# Channel_Display_v1.net
KiCad netlist of a schematic drawn in EAGLE
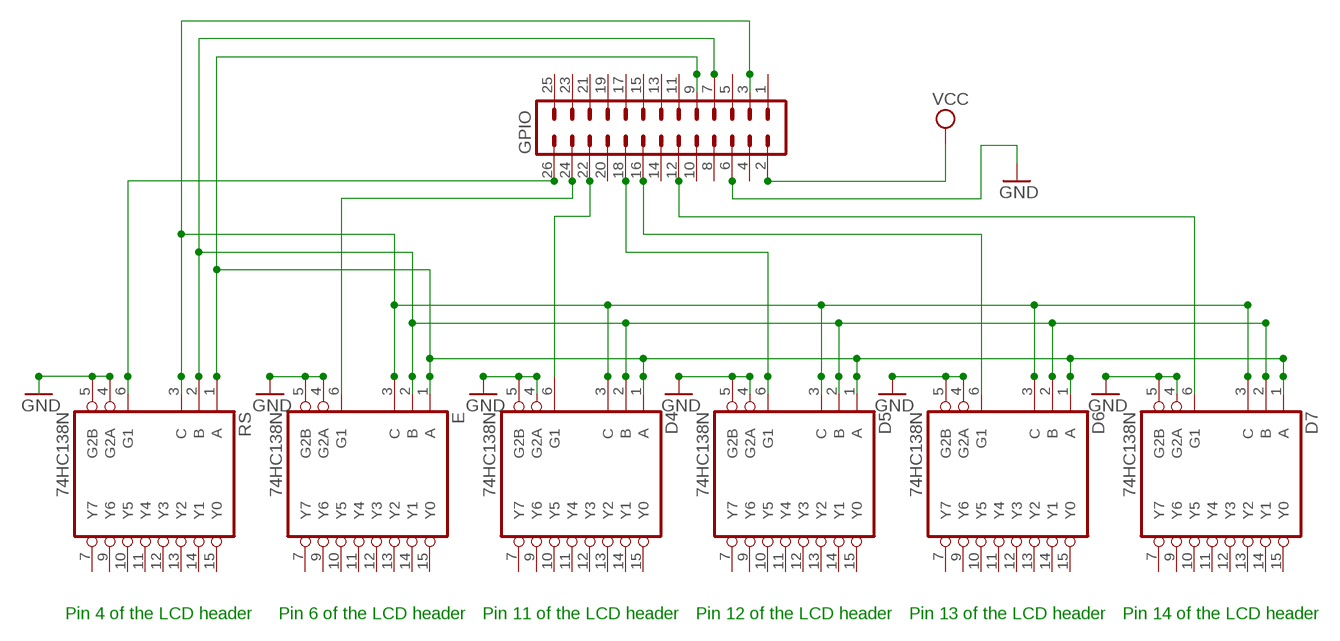
[diagram p0: schematic, sheet 1]

(export (version "E")
  (design (tool "Eeschema 10.0.6"))
  (components
    (comp (ref "D4")
      (value "74HC138N")
      (footprint "eagle-import:DIL16")
      (libsource (lib "eagle-import") (part "74138NHC"))
    )
    (comp (ref "D5")
      (value "74HC138N")
      (footprint "eagle-import:DIL16")
      (libsource (lib "eagle-import") (part "74138NHC"))
    )
    (comp (ref "D6")
      (value "74HC138N")
      (footprint "eagle-import:DIL16")
      (libsource (lib "eagle-import") (part "74138NHC"))
    )
    (comp (ref "D7")
      (value "74HC138N")
      (footprint "eagle-import:DIL16")
      (libsource (lib "eagle-import") (part "74138NHC"))
    )
    (comp (ref "E")
      (value "74HC138N")
      (footprint "eagle-import:DIL16")
      (libsource (lib "eagle-import") (part "74138NHC"))
    )
    (comp (ref "GPIO")
      (value "MA13-2")
      (footprint "eagle-import:MA13-2")
      (libsource (lib "eagle-import") (part "MA13-2"))
    )
    (comp (ref "RS")
      (value "74HC138N")
      (footprint "eagle-import:DIL16")
      (libsource (lib "eagle-import") (part "74138NHC"))
    )
  )
  (nets
    (net (code "1") (name "GND") (class "Default")
      (node (ref "D4") (pin "4") (pinfunction "G2A_4") (pintype "input"))
      (node (ref "D4") (pin "5") (pinfunction "G2B_5") (pintype "input"))
      (node (ref "D5") (pin "4") (pinfunction "G2A_4") (pintype "input"))
      (node (ref "D5") (pin "5") (pinfunction "G2B_5") (pintype "input"))
      (node (ref "D6") (pin "4") (pinfunction "G2A_4") (pintype "input"))
      (node (ref "D6") (pin "5") (pinfunction "G2B_5") (pintype "input"))
      (node (ref "D7") (pin "4") (pinfunction "G2A_4") (pintype "input"))
      (node (ref "D7") (pin "5") (pinfunction "G2B_5") (pintype "input"))
      (node (ref "E") (pin "4") (pinfunction "G2A_4") (pintype "input"))
      (node (ref "E") (pin "5") (pinfunction "G2B_5") (pintype "input"))
      (node (ref "GPIO") (pin "6") (pinfunction "6_6") (pintype "passive"))
      (node (ref "RS") (pin "4") (pinfunction "G2A_4") (pintype "input"))
      (node (ref "RS") (pin "5") (pinfunction "G2B_5") (pintype "input"))
    )
    (net (code "2") (name "Net-(D4A-A)") (class "Default")
      (node (ref "D4") (pin "1") (pinfunction "A_1") (pintype "input"))
      (node (ref "D5") (pin "1") (pinfunction "A_1") (pintype "input"))
      (node (ref "D6") (pin "1") (pinfunction "A_1") (pintype "input"))
      (node (ref "D7") (pin "1") (pinfunction "A_1") (pintype "input"))
      (node (ref "E") (pin "1") (pinfunction "A_1") (pintype "input"))
      (node (ref "GPIO") (pin "9") (pinfunction "9_9") (pintype "passive"))
      (node (ref "RS") (pin "1") (pinfunction "A_1") (pintype "input"))
    )
    (net (code "3") (name "Net-(D4A-B)") (class "Default")
      (node (ref "D4") (pin "2") (pinfunction "B_2") (pintype "input"))
      (node (ref "D5") (pin "2") (pinfunction "B_2") (pintype "input"))
      (node (ref "D6") (pin "2") (pinfunction "B_2") (pintype "input"))
      (node (ref "D7") (pin "2") (pinfunction "B_2") (pintype "input"))
      (node (ref "E") (pin "2") (pinfunction "B_2") (pintype "input"))
      (node (ref "GPIO") (pin "7") (pinfunction "7_7") (pintype "passive"))
      (node (ref "RS") (pin "2") (pinfunction "B_2") (pintype "input"))
    )
    (net (code "4") (name "Net-(D4A-C)") (class "Default")
      (node (ref "D4") (pin "3") (pinfunction "C_3") (pintype "input"))
      (node (ref "D5") (pin "3") (pinfunction "C_3") (pintype "input"))
      (node (ref "D6") (pin "3") (pinfunction "C_3") (pintype "input"))
      (node (ref "D7") (pin "3") (pinfunction "C_3") (pintype "input"))
      (node (ref "E") (pin "3") (pinfunction "C_3") (pintype "input"))
      (node (ref "GPIO") (pin "3") (pinfunction "3_3") (pintype "passive"))
      (node (ref "RS") (pin "3") (pinfunction "C_3") (pintype "input"))
    )
    (net (code "5") (name "Net-(D4A-G1)") (class "Default")
      (node (ref "D4") (pin "6") (pinfunction "G1_6") (pintype "input"))
      (node (ref "GPIO") (pin "22") (pinfunction "22_22") (pintype "passive"))
    )
    (net (code "6") (name "Net-(D5A-G1)") (class "Default")
      (node (ref "D5") (pin "6") (pinfunction "G1_6") (pintype "input"))
      (node (ref "GPIO") (pin "18") (pinfunction "18_18") (pintype "passive"))
    )
    (net (code "7") (name "Net-(RSA-G1)") (class "Default")
      (node (ref "GPIO") (pin "26") (pinfunction "26_26") (pintype "passive"))
      (node (ref "RS") (pin "6") (pinfunction "G1_6") (pintype "input"))
    )
    (net (code "8") (name "VCC") (class "Default")
      (node (ref "GPIO") (pin "2") (pinfunction "2_2") (pintype "passive"))
    )
    (net (code "9") (name "unconnected-(D4A-Y0-Pad15)") (class "Default")
      (node (ref "D4") (pin "15") (pinfunction "Y0_15") (pintype "output"))
    )
    (net (code "10") (name "unconnected-(D4A-Y1-Pad14)") (class "Default")
      (node (ref "D4") (pin "14") (pinfunction "Y1_14") (pintype "output"))
    )
    (net (code "11") (name "unconnected-(D4A-Y2-Pad13)") (class "Default")
      (node (ref "D4") (pin "13") (pinfunction "Y2_13") (pintype "output"))
    )
    (net (code "12") (name "unconnected-(D4A-Y3-Pad12)") (class "Default")
      (node (ref "D4") (pin "12") (pinfunction "Y3_12") (pintype "output"))
    )
    (net (code "13") (name "unconnected-(D4A-Y4-Pad11)") (class "Default")
      (node (ref "D4") (pin "11") (pinfunction "Y4_11") (pintype "output"))
    )
    (net (code "14") (name "unconnected-(D4A-Y5-Pad10)") (class "Default")
      (node (ref "D4") (pin "10") (pinfunction "Y5_10") (pintype "output"))
    )
    (net (code "15") (name "unconnected-(D4A-Y6-Pad9)") (class "Default")
      (node (ref "D4") (pin "9") (pinfunction "Y6_9") (pintype "output"))
    )
    (net (code "16") (name "unconnected-(D4A-Y7-Pad7)") (class "Default")
      (node (ref "D4") (pin "7") (pinfunction "Y7_7") (pintype "output"))
    )
    (net (code "17") (name "unconnected-(D5A-Y0-Pad15)") (class "Default")
      (node (ref "D5") (pin "15") (pinfunction "Y0_15") (pintype "output"))
    )
    (net (code "18") (name "unconnected-(D5A-Y1-Pad14)") (class "Default")
      (node (ref "D5") (pin "14") (pinfunction "Y1_14") (pintype "output"))
    )
    (net (code "19") (name "unconnected-(D5A-Y2-Pad13)") (class "Default")
      (node (ref "D5") (pin "13") (pinfunction "Y2_13") (pintype "output"))
    )
    (net (code "20") (name "unconnected-(D5A-Y3-Pad12)") (class "Default")
      (node (ref "D5") (pin "12") (pinfunction "Y3_12") (pintype "output"))
    )
    (net (code "21") (name "unconnected-(D5A-Y4-Pad11)") (class "Default")
      (node (ref "D5") (pin "11") (pinfunction "Y4_11") (pintype "output"))
    )
    (net (code "22") (name "unconnected-(D5A-Y5-Pad10)") (class "Default")
      (node (ref "D5") (pin "10") (pinfunction "Y5_10") (pintype "output"))
    )
    (net (code "23") (name "unconnected-(D5A-Y6-Pad9)") (class "Default")
      (node (ref "D5") (pin "9") (pinfunction "Y6_9") (pintype "output"))
    )
    (net (code "24") (name "unconnected-(D5A-Y7-Pad7)") (class "Default")
      (node (ref "D5") (pin "7") (pinfunction "Y7_7") (pintype "output"))
    )
    (net (code "25") (name "unconnected-(D6A-G1-Pad6)") (class "Default")
      (node (ref "D6") (pin "6") (pinfunction "G1_6") (pintype "input"))
    )
    (net (code "26") (name "unconnected-(D6A-Y0-Pad15)") (class "Default")
      (node (ref "D6") (pin "15") (pinfunction "Y0_15") (pintype "output"))
    )
    (net (code "27") (name "unconnected-(D6A-Y1-Pad14)") (class "Default")
      (node (ref "D6") (pin "14") (pinfunction "Y1_14") (pintype "output"))
    )
    (net (code "28") (name "unconnected-(D6A-Y2-Pad13)") (class "Default")
      (node (ref "D6") (pin "13") (pinfunction "Y2_13") (pintype "output"))
    )
    (net (code "29") (name "unconnected-(D6A-Y3-Pad12)") (class "Default")
      (node (ref "D6") (pin "12") (pinfunction "Y3_12") (pintype "output"))
    )
    (net (code "30") (name "unconnected-(D6A-Y4-Pad11)") (class "Default")
      (node (ref "D6") (pin "11") (pinfunction "Y4_11") (pintype "output"))
    )
    (net (code "31") (name "unconnected-(D6A-Y5-Pad10)") (class "Default")
      (node (ref "D6") (pin "10") (pinfunction "Y5_10") (pintype "output"))
    )
    (net (code "32") (name "unconnected-(D6A-Y6-Pad9)") (class "Default")
      (node (ref "D6") (pin "9") (pinfunction "Y6_9") (pintype "output"))
    )
    (net (code "33") (name "unconnected-(D6A-Y7-Pad7)") (class "Default")
      (node (ref "D6") (pin "7") (pinfunction "Y7_7") (pintype "output"))
    )
    (net (code "34") (name "unconnected-(D7A-G1-Pad6)") (class "Default")
      (node (ref "D7") (pin "6") (pinfunction "G1_6") (pintype "input"))
    )
    (net (code "35") (name "unconnected-(D7A-Y0-Pad15)") (class "Default")
      (node (ref "D7") (pin "15") (pinfunction "Y0_15") (pintype "output"))
    )
    (net (code "36") (name "unconnected-(D7A-Y1-Pad14)") (class "Default")
      (node (ref "D7") (pin "14") (pinfunction "Y1_14") (pintype "output"))
    )
    (net (code "37") (name "unconnected-(D7A-Y2-Pad13)") (class "Default")
      (node (ref "D7") (pin "13") (pinfunction "Y2_13") (pintype "output"))
    )
    (net (code "38") (name "unconnected-(D7A-Y3-Pad12)") (class "Default")
      (node (ref "D7") (pin "12") (pinfunction "Y3_12") (pintype "output"))
    )
    (net (code "39") (name "unconnected-(D7A-Y4-Pad11)") (class "Default")
      (node (ref "D7") (pin "11") (pinfunction "Y4_11") (pintype "output"))
    )
    (net (code "40") (name "unconnected-(D7A-Y5-Pad10)") (class "Default")
      (node (ref "D7") (pin "10") (pinfunction "Y5_10") (pintype "output"))
    )
    (net (code "41") (name "unconnected-(D7A-Y6-Pad9)") (class "Default")
      (node (ref "D7") (pin "9") (pinfunction "Y6_9") (pintype "output"))
    )
    (net (code "42") (name "unconnected-(D7A-Y7-Pad7)") (class "Default")
      (node (ref "D7") (pin "7") (pinfunction "Y7_7") (pintype "output"))
    )
    (net (code "43") (name "unconnected-(EA-G1-Pad6)") (class "Default")
      (node (ref "E") (pin "6") (pinfunction "G1_6") (pintype "input"))
    )
    (net (code "44") (name "unconnected-(EA-Y0-Pad15)") (class "Default")
      (node (ref "E") (pin "15") (pinfunction "Y0_15") (pintype "output"))
    )
    (net (code "45") (name "unconnected-(EA-Y1-Pad14)") (class "Default")
      (node (ref "E") (pin "14") (pinfunction "Y1_14") (pintype "output"))
    )
    (net (code "46") (name "unconnected-(EA-Y2-Pad13)") (class "Default")
      (node (ref "E") (pin "13") (pinfunction "Y2_13") (pintype "output"))
    )
    (net (code "47") (name "unconnected-(EA-Y3-Pad12)") (class "Default")
      (node (ref "E") (pin "12") (pinfunction "Y3_12") (pintype "output"))
    )
    (net (code "48") (name "unconnected-(EA-Y4-Pad11)") (class "Default")
      (node (ref "E") (pin "11") (pinfunction "Y4_11") (pintype "output"))
    )
    (net (code "49") (name "unconnected-(EA-Y5-Pad10)") (class "Default")
      (node (ref "E") (pin "10") (pinfunction "Y5_10") (pintype "output"))
    )
    (net (code "50") (name "unconnected-(EA-Y6-Pad9)") (class "Default")
      (node (ref "E") (pin "9") (pinfunction "Y6_9") (pintype "output"))
    )
    (net (code "51") (name "unconnected-(EA-Y7-Pad7)") (class "Default")
      (node (ref "E") (pin "7") (pinfunction "Y7_7") (pintype "output"))
    )
    (net (code "52") (name "unconnected-(GPIO-Pad1)") (class "Default")
      (node (ref "GPIO") (pin "1") (pinfunction "1_1") (pintype "passive"))
    )
    (net (code "53") (name "unconnected-(GPIO-Pad4)") (class "Default")
      (node (ref "GPIO") (pin "4") (pinfunction "4_4") (pintype "passive"))
    )
    (net (code "54") (name "unconnected-(GPIO-Pad5)") (class "Default")
      (node (ref "GPIO") (pin "5") (pinfunction "5_5") (pintype "passive"))
    )
    (net (code "55") (name "unconnected-(GPIO-Pad8)") (class "Default")
      (node (ref "GPIO") (pin "8") (pinfunction "8_8") (pintype "passive"))
    )
    (net (code "56") (name "unconnected-(GPIO-Pad10)") (class "Default")
      (node (ref "GPIO") (pin "10") (pinfunction "10_10") (pintype "passive"))
    )
    (net (code "57") (name "unconnected-(GPIO-Pad11)") (class "Default")
      (node (ref "GPIO") (pin "11") (pinfunction "11_11") (pintype "passive"))
    )
    (net (code "58") (name "unconnected-(GPIO-Pad12)") (class "Default")
      (node (ref "GPIO") (pin "12") (pinfunction "12_12") (pintype "passive"))
    )
    (net (code "59") (name "unconnected-(GPIO-Pad13)") (class "Default")
      (node (ref "GPIO") (pin "13") (pinfunction "13_13") (pintype "passive"))
    )
    (net (code "60") (name "unconnected-(GPIO-Pad14)") (class "Default")
      (node (ref "GPIO") (pin "14") (pinfunction "14_14") (pintype "passive"))
    )
    (net (code "61") (name "unconnected-(GPIO-Pad15)") (class "Default")
      (node (ref "GPIO") (pin "15") (pinfunction "15_15") (pintype "passive"))
    )
    (net (code "62") (name "unconnected-(GPIO-Pad16)") (class "Default")
      (node (ref "GPIO") (pin "16") (pinfunction "16_16") (pintype "passive"))
    )
    (net (code "63") (name "unconnected-(GPIO-Pad17)") (class "Default")
      (node (ref "GPIO") (pin "17") (pinfunction "17_17") (pintype "passive"))
    )
    (net (code "64") (name "unconnected-(GPIO-Pad19)") (class "Default")
      (node (ref "GPIO") (pin "19") (pinfunction "19_19") (pintype "passive"))
    )
    (net (code "65") (name "unconnected-(GPIO-Pad20)") (class "Default")
      (node (ref "GPIO") (pin "20") (pinfunction "20_20") (pintype "passive"))
    )
    (net (code "66") (name "unconnected-(GPIO-Pad21)") (class "Default")
      (node (ref "GPIO") (pin "21") (pinfunction "21_21") (pintype "passive"))
    )
    (net (code "67") (name "unconnected-(GPIO-Pad23)") (class "Default")
      (node (ref "GPIO") (pin "23") (pinfunction "23_23") (pintype "passive"))
    )
    (net (code "68") (name "unconnected-(GPIO-Pad24)") (class "Default")
      (node (ref "GPIO") (pin "24") (pinfunction "24_24") (pintype "passive"))
    )
    (net (code "69") (name "unconnected-(GPIO-Pad25)") (class "Default")
      (node (ref "GPIO") (pin "25") (pinfunction "25_25") (pintype "passive"))
    )
    (net (code "70") (name "unconnected-(RSA-Y0-Pad15)") (class "Default")
      (node (ref "RS") (pin "15") (pinfunction "Y0_15") (pintype "output"))
    )
    (net (code "71") (name "unconnected-(RSA-Y1-Pad14)") (class "Default")
      (node (ref "RS") (pin "14") (pinfunction "Y1_14") (pintype "output"))
    )
    (net (code "72") (name "unconnected-(RSA-Y2-Pad13)") (class "Default")
      (node (ref "RS") (pin "13") (pinfunction "Y2_13") (pintype "output"))
    )
    (net (code "73") (name "unconnected-(RSA-Y3-Pad12)") (class "Default")
      (node (ref "RS") (pin "12") (pinfunction "Y3_12") (pintype "output"))
    )
    (net (code "74") (name "unconnected-(RSA-Y4-Pad11)") (class "Default")
      (node (ref "RS") (pin "11") (pinfunction "Y4_11") (pintype "output"))
    )
    (net (code "75") (name "unconnected-(RSA-Y5-Pad10)") (class "Default")
      (node (ref "RS") (pin "10") (pinfunction "Y5_10") (pintype "output"))
    )
    (net (code "76") (name "unconnected-(RSA-Y6-Pad9)") (class "Default")
      (node (ref "RS") (pin "9") (pinfunction "Y6_9") (pintype "output"))
    )
    (net (code "77") (name "unconnected-(RSA-Y7-Pad7)") (class "Default")
      (node (ref "RS") (pin "7") (pinfunction "Y7_7") (pintype "output"))
    )
  )
)
